# DE-140824_01.net
KiCad netlist of a schematic drawn in Altium Designer
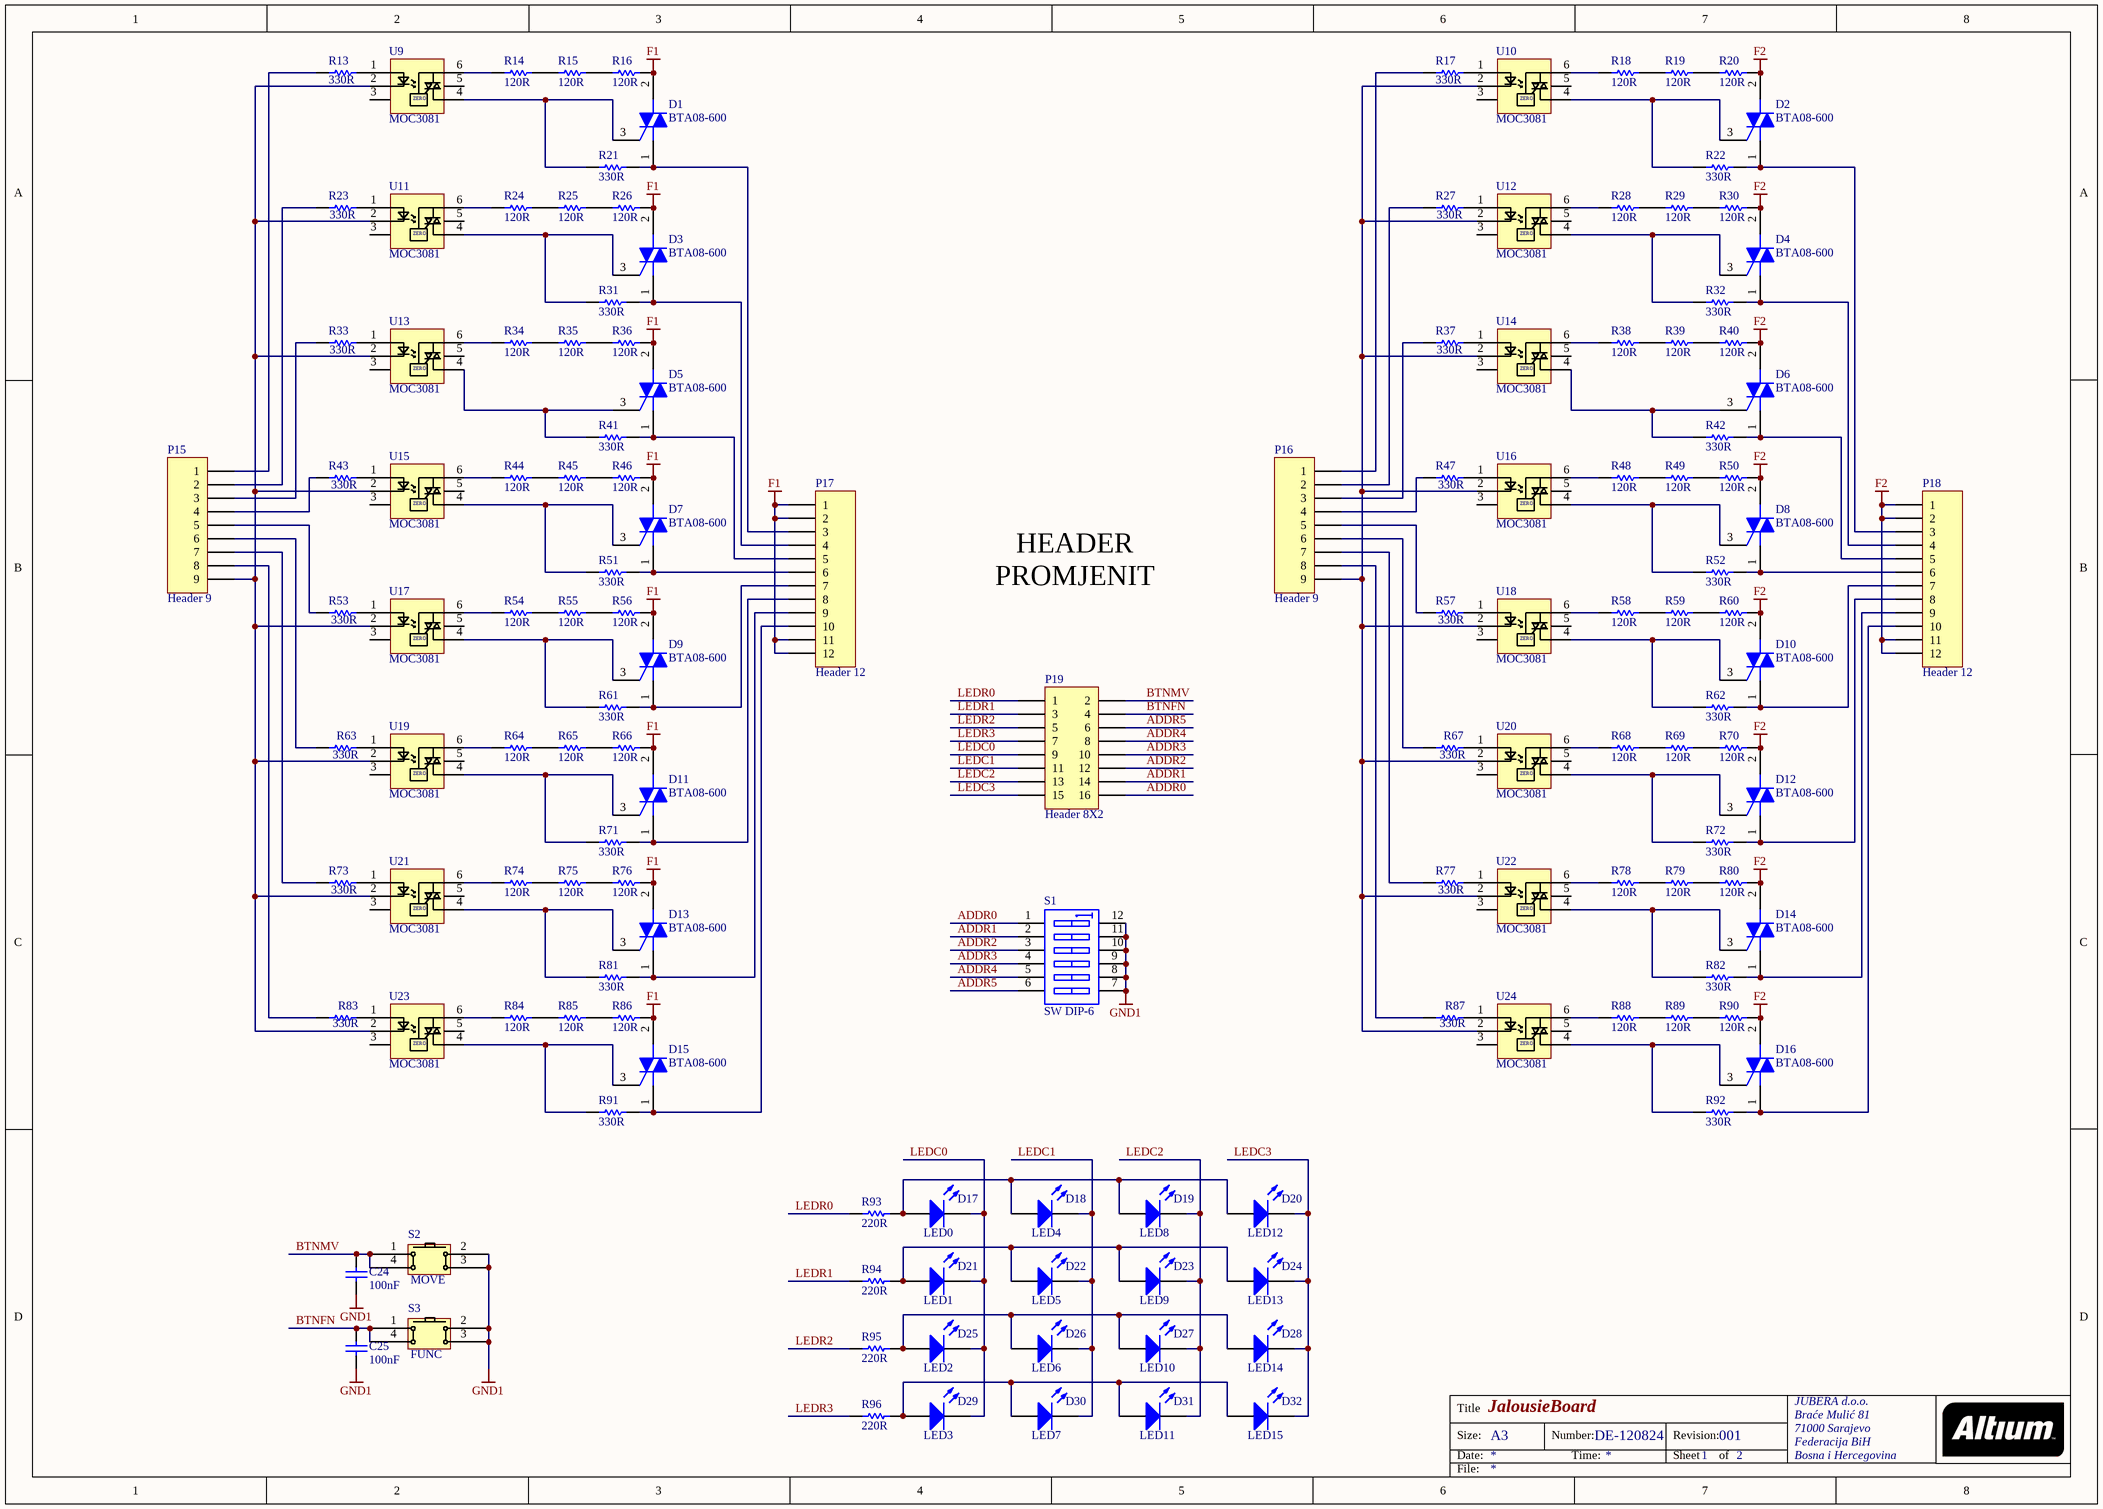
[diagram p0: DE-140824_01.SchDoc]

(export (version "E")
  (design (tool "Eeschema 10.0.6"))
  (components
    (comp (ref "C24")
      (value "100nF")
      (footprint "0603")
      (description "Ceramic Chip Capacitor - Standard")
      (fields (field (name "Comment") "C0603") (field (name "PUBLISHER") "Altium Limited"))
      (libsource (lib "DE-120824") (part "C0603"))
    )
    (comp (ref "C25")
      (value "100nF")
      (footprint "0603")
      (description "Ceramic Chip Capacitor - Standard")
      (fields (field (name "Comment") "C0603") (field (name "PUBLISHER") "Altium Limited"))
      (libsource (lib "DE-120824") (part "C0603"))
    )
    (comp (ref "D1")
      (value "BTA08-600")
      (footprint "ONSC-TO-220-3-221A-07")
      (description "Triacs, Silicon Bidirectional Thyristor, 3-Pin TO-220, Pb-Free, Tube")
      (fields (field (name "MANUFACTURER") "On Semiconductor") (field (name "PARTNUMBER") "BTA08-600BW3G"))
      (libsource (lib "DE-120824") (part "BTA08-600BW3G"))
    )
    (comp (ref "D2")
      (value "BTA08-600")
      (footprint "ONSC-TO-220-3-221A-07")
      (description "Triacs, Silicon Bidirectional Thyristor, 3-Pin TO-220, Pb-Free, Tube")
      (fields (field (name "MANUFACTURER") "On Semiconductor") (field (name "PARTNUMBER") "BTA08-600BW3G"))
      (libsource (lib "DE-120824") (part "BTA08-600BW3G"))
    )
    (comp (ref "D3")
      (value "BTA08-600")
      (footprint "ONSC-TO-220-3-221A-07")
      (description "Triacs, Silicon Bidirectional Thyristor, 3-Pin TO-220, Pb-Free, Tube")
      (fields (field (name "MANUFACTURER") "On Semiconductor") (field (name "PARTNUMBER") "BTA08-600BW3G"))
      (libsource (lib "DE-120824") (part "BTA08-600BW3G"))
    )
    (comp (ref "D4")
      (value "BTA08-600")
      (footprint "ONSC-TO-220-3-221A-07")
      (description "Triacs, Silicon Bidirectional Thyristor, 3-Pin TO-220, Pb-Free, Tube")
      (fields (field (name "MANUFACTURER") "On Semiconductor") (field (name "PARTNUMBER") "BTA08-600BW3G"))
      (libsource (lib "DE-120824") (part "BTA08-600BW3G"))
    )
    (comp (ref "D5")
      (value "BTA08-600")
      (footprint "ONSC-TO-220-3-221A-07")
      (description "Triacs, Silicon Bidirectional Thyristor, 3-Pin TO-220, Pb-Free, Tube")
      (fields (field (name "MANUFACTURER") "On Semiconductor") (field (name "PARTNUMBER") "BTA08-600BW3G"))
      (libsource (lib "DE-120824") (part "BTA08-600BW3G"))
    )
    (comp (ref "D6")
      (value "BTA08-600")
      (footprint "ONSC-TO-220-3-221A-07")
      (description "Triacs, Silicon Bidirectional Thyristor, 3-Pin TO-220, Pb-Free, Tube")
      (fields (field (name "MANUFACTURER") "On Semiconductor") (field (name "PARTNUMBER") "BTA08-600BW3G"))
      (libsource (lib "DE-120824") (part "BTA08-600BW3G"))
    )
    (comp (ref "D7")
      (value "BTA08-600")
      (footprint "ONSC-TO-220-3-221A-07")
      (description "Triacs, Silicon Bidirectional Thyristor, 3-Pin TO-220, Pb-Free, Tube")
      (fields (field (name "MANUFACTURER") "On Semiconductor") (field (name "PARTNUMBER") "BTA08-600BW3G"))
      (libsource (lib "DE-120824") (part "BTA08-600BW3G"))
    )
    (comp (ref "D8")
      (value "BTA08-600")
      (footprint "ONSC-TO-220-3-221A-07")
      (description "Triacs, Silicon Bidirectional Thyristor, 3-Pin TO-220, Pb-Free, Tube")
      (fields (field (name "MANUFACTURER") "On Semiconductor") (field (name "PARTNUMBER") "BTA08-600BW3G"))
      (libsource (lib "DE-120824") (part "BTA08-600BW3G"))
    )
    (comp (ref "D9")
      (value "BTA08-600")
      (footprint "ONSC-TO-220-3-221A-07")
      (description "Triacs, Silicon Bidirectional Thyristor, 3-Pin TO-220, Pb-Free, Tube")
      (fields (field (name "MANUFACTURER") "On Semiconductor") (field (name "PARTNUMBER") "BTA08-600BW3G"))
      (libsource (lib "DE-120824") (part "BTA08-600BW3G"))
    )
    (comp (ref "D10")
      (value "BTA08-600")
      (footprint "ONSC-TO-220-3-221A-07")
      (description "Triacs, Silicon Bidirectional Thyristor, 3-Pin TO-220, Pb-Free, Tube")
      (fields (field (name "MANUFACTURER") "On Semiconductor") (field (name "PARTNUMBER") "BTA08-600BW3G"))
      (libsource (lib "DE-120824") (part "BTA08-600BW3G"))
    )
    (comp (ref "D11")
      (value "BTA08-600")
      (footprint "ONSC-TO-220-3-221A-07")
      (description "Triacs, Silicon Bidirectional Thyristor, 3-Pin TO-220, Pb-Free, Tube")
      (fields (field (name "MANUFACTURER") "On Semiconductor") (field (name "PARTNUMBER") "BTA08-600BW3G"))
      (libsource (lib "DE-120824") (part "BTA08-600BW3G"))
    )
    (comp (ref "D12")
      (value "BTA08-600")
      (footprint "ONSC-TO-220-3-221A-07")
      (description "Triacs, Silicon Bidirectional Thyristor, 3-Pin TO-220, Pb-Free, Tube")
      (fields (field (name "MANUFACTURER") "On Semiconductor") (field (name "PARTNUMBER") "BTA08-600BW3G"))
      (libsource (lib "DE-120824") (part "BTA08-600BW3G"))
    )
    (comp (ref "D13")
      (value "BTA08-600")
      (footprint "ONSC-TO-220-3-221A-07")
      (description "Triacs, Silicon Bidirectional Thyristor, 3-Pin TO-220, Pb-Free, Tube")
      (fields (field (name "MANUFACTURER") "On Semiconductor") (field (name "PARTNUMBER") "BTA08-600BW3G"))
      (libsource (lib "DE-120824") (part "BTA08-600BW3G"))
    )
    (comp (ref "D14")
      (value "BTA08-600")
      (footprint "ONSC-TO-220-3-221A-07")
      (description "Triacs, Silicon Bidirectional Thyristor, 3-Pin TO-220, Pb-Free, Tube")
      (fields (field (name "MANUFACTURER") "On Semiconductor") (field (name "PARTNUMBER") "BTA08-600BW3G"))
      (libsource (lib "DE-120824") (part "BTA08-600BW3G"))
    )
    (comp (ref "D15")
      (value "BTA08-600")
      (footprint "ONSC-TO-220-3-221A-07")
      (description "Triacs, Silicon Bidirectional Thyristor, 3-Pin TO-220, Pb-Free, Tube")
      (fields (field (name "MANUFACTURER") "On Semiconductor") (field (name "PARTNUMBER") "BTA08-600BW3G"))
      (libsource (lib "DE-120824") (part "BTA08-600BW3G"))
    )
    (comp (ref "D16")
      (value "BTA08-600")
      (footprint "ONSC-TO-220-3-221A-07")
      (description "Triacs, Silicon Bidirectional Thyristor, 3-Pin TO-220, Pb-Free, Tube")
      (fields (field (name "MANUFACTURER") "On Semiconductor") (field (name "PARTNUMBER") "BTA08-600BW3G"))
      (libsource (lib "DE-120824") (part "BTA08-600BW3G"))
    )
    (comp (ref "D17")
      (value "LED0")
      (footprint "1.6X0.8X0.8")
      (description "Blue Surface Mount Chip LED, Blue")
      (fields (field (name "PUBLISHER") "Altium Limited"))
      (libsource (lib "DE-120824") (part "HSMB-C190"))
    )
    (comp (ref "D18")
      (value "LED4")
      (footprint "1.6X0.8X0.8")
      (description "Blue Surface Mount Chip LED, Blue")
      (fields (field (name "PUBLISHER") "Altium Limited"))
      (libsource (lib "DE-120824") (part "HSMB-C190"))
    )
    (comp (ref "D19")
      (value "LED8")
      (footprint "1.6X0.8X0.8")
      (description "Blue Surface Mount Chip LED, Blue")
      (fields (field (name "PUBLISHER") "Altium Limited"))
      (libsource (lib "DE-120824") (part "HSMB-C190"))
    )
    (comp (ref "D20")
      (value "LED12")
      (footprint "1.6X0.8X0.8")
      (description "Blue Surface Mount Chip LED, Blue")
      (fields (field (name "PUBLISHER") "Altium Limited"))
      (libsource (lib "DE-120824") (part "HSMB-C190"))
    )
    (comp (ref "D21")
      (value "LED1")
      (footprint "1.6X0.8X0.8")
      (description "Blue Surface Mount Chip LED, Blue")
      (fields (field (name "PUBLISHER") "Altium Limited"))
      (libsource (lib "DE-120824") (part "HSMB-C190"))
    )
    (comp (ref "D22")
      (value "LED5")
      (footprint "1.6X0.8X0.8")
      (description "Blue Surface Mount Chip LED, Blue")
      (fields (field (name "PUBLISHER") "Altium Limited"))
      (libsource (lib "DE-120824") (part "HSMB-C190"))
    )
    (comp (ref "D23")
      (value "LED9")
      (footprint "1.6X0.8X0.8")
      (description "Blue Surface Mount Chip LED, Blue")
      (fields (field (name "PUBLISHER") "Altium Limited"))
      (libsource (lib "DE-120824") (part "HSMB-C190"))
    )
    (comp (ref "D24")
      (value "LED13")
      (footprint "1.6X0.8X0.8")
      (description "Blue Surface Mount Chip LED, Blue")
      (fields (field (name "PUBLISHER") "Altium Limited"))
      (libsource (lib "DE-120824") (part "HSMB-C190"))
    )
    (comp (ref "D25")
      (value "LED2")
      (footprint "1.6X0.8X0.8")
      (description "Blue Surface Mount Chip LED, Blue")
      (fields (field (name "PUBLISHER") "Altium Limited"))
      (libsource (lib "DE-120824") (part "HSMB-C190"))
    )
    (comp (ref "D26")
      (value "LED6")
      (footprint "1.6X0.8X0.8")
      (description "Blue Surface Mount Chip LED, Blue")
      (fields (field (name "PUBLISHER") "Altium Limited"))
      (libsource (lib "DE-120824") (part "HSMB-C190"))
    )
    (comp (ref "D27")
      (value "LED10")
      (footprint "1.6X0.8X0.8")
      (description "Blue Surface Mount Chip LED, Blue")
      (fields (field (name "PUBLISHER") "Altium Limited"))
      (libsource (lib "DE-120824") (part "HSMB-C190"))
    )
    (comp (ref "D28")
      (value "LED14")
      (footprint "1.6X0.8X0.8")
      (description "Blue Surface Mount Chip LED, Blue")
      (fields (field (name "PUBLISHER") "Altium Limited"))
      (libsource (lib "DE-120824") (part "HSMB-C190"))
    )
    (comp (ref "D29")
      (value "LED3")
      (footprint "1.6X0.8X0.8")
      (description "Blue Surface Mount Chip LED, Blue")
      (fields (field (name "PUBLISHER") "Altium Limited"))
      (libsource (lib "DE-120824") (part "HSMB-C190"))
    )
    (comp (ref "D30")
      (value "LED7")
      (footprint "1.6X0.8X0.8")
      (description "Blue Surface Mount Chip LED, Blue")
      (fields (field (name "PUBLISHER") "Altium Limited"))
      (libsource (lib "DE-120824") (part "HSMB-C190"))
    )
    (comp (ref "D31")
      (value "LED11")
      (footprint "1.6X0.8X0.8")
      (description "Blue Surface Mount Chip LED, Blue")
      (fields (field (name "PUBLISHER") "Altium Limited"))
      (libsource (lib "DE-120824") (part "HSMB-C190"))
    )
    (comp (ref "D32")
      (value "LED15")
      (footprint "1.6X0.8X0.8")
      (description "Blue Surface Mount Chip LED, Blue")
      (fields (field (name "PUBLISHER") "Altium Limited"))
      (libsource (lib "DE-120824") (part "HSMB-C190"))
    )
    (comp (ref "P15")
      (value "Header 9")
      (footprint "HDR1X9")
      (description "Header, 9-Pin")
      (fields (field (name "PUBLISHER") "Altium Limited"))
      (libsource (lib "Miscellaneous Connectors") (part "Header 9"))
    )
    (comp (ref "P16")
      (value "Header 9")
      (footprint "HDR1X9")
      (description "Header, 9-Pin")
      (fields (field (name "PUBLISHER") "Altium Limited"))
      (libsource (lib "Miscellaneous Connectors") (part "Header 9"))
    )
    (comp (ref "P17")
      (value "Header 12")
      (footprint "HDR1X12")
      (description "Header, 12-Pin")
      (fields (field (name "PUBLISHER") "Altium Limited"))
      (libsource (lib "Miscellaneous Connectors") (part "Header 12"))
    )
    (comp (ref "P18")
      (value "Header 12")
      (footprint "HDR1X12")
      (description "Header, 12-Pin")
      (fields (field (name "PUBLISHER") "Altium Limited"))
      (libsource (lib "Miscellaneous Connectors") (part "Header 12"))
    )
    (comp (ref "P19")
      (value "Header 8X2")
      (footprint "HDR2X8")
      (description "Header, 8-Pin, Dual row")
      (fields (field (name "PUBLISHER") "Altium Limited"))
      (libsource (lib "Miscellaneous Connectors") (part "Header 8X2"))
    )
    (comp (ref "R13")
      (value "330R")
      (footprint "ERA-0603")
      (fields (field (name "PUBLISHER") "Altium Limited"))
      (libsource (lib "DE-120824") (part "ERA3Y"))
    )
    (comp (ref "R14")
      (value "120R")
      (footprint "ERA-0805")
      (fields (field (name "PUBLISHER") "Altium Limited"))
      (libsource (lib "DE-120824") (part "ERAS"))
    )
    (comp (ref "R15")
      (value "120R")
      (footprint "ERA-0805")
      (fields (field (name "PUBLISHER") "Altium Limited"))
      (libsource (lib "DE-120824") (part "ERAS"))
    )
    (comp (ref "R16")
      (value "120R")
      (footprint "ERA-0805")
      (fields (field (name "PUBLISHER") "Altium Limited"))
      (libsource (lib "DE-120824") (part "ERAS"))
    )
    (comp (ref "R17")
      (value "330R")
      (footprint "ERA-0603")
      (fields (field (name "PUBLISHER") "Altium Limited"))
      (libsource (lib "DE-120824") (part "ERA3Y"))
    )
    (comp (ref "R18")
      (value "120R")
      (footprint "ERA-0805")
      (fields (field (name "PUBLISHER") "Altium Limited"))
      (libsource (lib "DE-120824") (part "ERAS"))
    )
    (comp (ref "R19")
      (value "120R")
      (footprint "ERA-0805")
      (fields (field (name "PUBLISHER") "Altium Limited"))
      (libsource (lib "DE-120824") (part "ERAS"))
    )
    (comp (ref "R20")
      (value "120R")
      (footprint "ERA-0805")
      (fields (field (name "PUBLISHER") "Altium Limited"))
      (libsource (lib "DE-120824") (part "ERAS"))
    )
    (comp (ref "R21")
      (value "330R")
      (footprint "ERA-0805")
      (fields (field (name "PUBLISHER") "Altium Limited"))
      (libsource (lib "DE-120824") (part "ERAS"))
    )
    (comp (ref "R22")
      (value "330R")
      (footprint "ERA-0805")
      (fields (field (name "PUBLISHER") "Altium Limited"))
      (libsource (lib "DE-120824") (part "ERAS"))
    )
    (comp (ref "R23")
      (value "330R")
      (footprint "ERA-0603")
      (fields (field (name "PUBLISHER") "Altium Limited"))
      (libsource (lib "DE-120824") (part "ERA3Y"))
    )
    (comp (ref "R24")
      (value "120R")
      (footprint "ERA-0805")
      (fields (field (name "PUBLISHER") "Altium Limited"))
      (libsource (lib "DE-120824") (part "ERAS"))
    )
    (comp (ref "R25")
      (value "120R")
      (footprint "ERA-0805")
      (fields (field (name "PUBLISHER") "Altium Limited"))
      (libsource (lib "DE-120824") (part "ERAS"))
    )
    (comp (ref "R26")
      (value "120R")
      (footprint "ERA-0805")
      (fields (field (name "PUBLISHER") "Altium Limited"))
      (libsource (lib "DE-120824") (part "ERAS"))
    )
    (comp (ref "R27")
      (value "330R")
      (footprint "ERA-0603")
      (fields (field (name "PUBLISHER") "Altium Limited"))
      (libsource (lib "DE-120824") (part "ERA3Y"))
    )
    (comp (ref "R28")
      (value "120R")
      (footprint "ERA-0805")
      (fields (field (name "PUBLISHER") "Altium Limited"))
      (libsource (lib "DE-120824") (part "ERAS"))
    )
    (comp (ref "R29")
      (value "120R")
      (footprint "ERA-0805")
      (fields (field (name "PUBLISHER") "Altium Limited"))
      (libsource (lib "DE-120824") (part "ERAS"))
    )
    (comp (ref "R30")
      (value "120R")
      (footprint "ERA-0805")
      (fields (field (name "PUBLISHER") "Altium Limited"))
      (libsource (lib "DE-120824") (part "ERAS"))
    )
    (comp (ref "R31")
      (value "330R")
      (footprint "ERA-0805")
      (fields (field (name "PUBLISHER") "Altium Limited"))
      (libsource (lib "DE-120824") (part "ERAS"))
    )
    (comp (ref "R32")
      (value "330R")
      (footprint "ERA-0805")
      (fields (field (name "PUBLISHER") "Altium Limited"))
      (libsource (lib "DE-120824") (part "ERAS"))
    )
    (comp (ref "R33")
      (value "330R")
      (footprint "ERA-0603")
      (fields (field (name "PUBLISHER") "Altium Limited"))
      (libsource (lib "DE-120824") (part "ERA3Y"))
    )
    (comp (ref "R34")
      (value "120R")
      (footprint "ERA-0805")
      (fields (field (name "PUBLISHER") "Altium Limited"))
      (libsource (lib "DE-120824") (part "ERAS"))
    )
    (comp (ref "R35")
      (value "120R")
      (footprint "ERA-0805")
      (fields (field (name "PUBLISHER") "Altium Limited"))
      (libsource (lib "DE-120824") (part "ERAS"))
    )
    (comp (ref "R36")
      (value "120R")
      (footprint "ERA-0805")
      (fields (field (name "PUBLISHER") "Altium Limited"))
      (libsource (lib "DE-120824") (part "ERAS"))
    )
    (comp (ref "R37")
      (value "330R")
      (footprint "ERA-0603")
      (fields (field (name "PUBLISHER") "Altium Limited"))
      (libsource (lib "DE-120824") (part "ERA3Y"))
    )
    (comp (ref "R38")
      (value "120R")
      (footprint "ERA-0805")
      (fields (field (name "PUBLISHER") "Altium Limited"))
      (libsource (lib "DE-120824") (part "ERAS"))
    )
    (comp (ref "R39")
      (value "120R")
      (footprint "ERA-0805")
      (fields (field (name "PUBLISHER") "Altium Limited"))
      (libsource (lib "DE-120824") (part "ERAS"))
    )
    (comp (ref "R40")
      (value "120R")
      (footprint "ERA-0805")
      (fields (field (name "PUBLISHER") "Altium Limited"))
      (libsource (lib "DE-120824") (part "ERAS"))
    )
    (comp (ref "R41")
      (value "330R")
      (footprint "ERA-0805")
      (fields (field (name "PUBLISHER") "Altium Limited"))
      (libsource (lib "DE-120824") (part "ERAS"))
    )
    (comp (ref "R42")
      (value "330R")
      (footprint "ERA-0805")
      (fields (field (name "PUBLISHER") "Altium Limited"))
      (libsource (lib "DE-120824") (part "ERAS"))
    )
    (comp (ref "R43")
      (value "330R")
      (footprint "ERA-0603")
      (fields (field (name "PUBLISHER") "Altium Limited"))
      (libsource (lib "DE-120824") (part "ERA3Y"))
    )
    (comp (ref "R44")
      (value "120R")
      (footprint "ERA-0805")
      (fields (field (name "PUBLISHER") "Altium Limited"))
      (libsource (lib "DE-120824") (part "ERAS"))
    )
    (comp (ref "R45")
      (value "120R")
      (footprint "ERA-0805")
      (fields (field (name "PUBLISHER") "Altium Limited"))
      (libsource (lib "DE-120824") (part "ERAS"))
    )
    (comp (ref "R46")
      (value "120R")
      (footprint "ERA-0805")
      (fields (field (name "PUBLISHER") "Altium Limited"))
      (libsource (lib "DE-120824") (part "ERAS"))
    )
    (comp (ref "R47")
      (value "330R")
      (footprint "ERA-0603")
      (fields (field (name "PUBLISHER") "Altium Limited"))
      (libsource (lib "DE-120824") (part "ERA3Y"))
    )
    (comp (ref "R48")
      (value "120R")
      (footprint "ERA-0805")
      (fields (field (name "PUBLISHER") "Altium Limited"))
      (libsource (lib "DE-120824") (part "ERAS"))
    )
    (comp (ref "R49")
      (value "120R")
      (footprint "ERA-0805")
      (fields (field (name "PUBLISHER") "Altium Limited"))
      (libsource (lib "DE-120824") (part "ERAS"))
    )
    (comp (ref "R50")
      (value "120R")
      (footprint "ERA-0805")
      (fields (field (name "PUBLISHER") "Altium Limited"))
      (libsource (lib "DE-120824") (part "ERAS"))
    )
    (comp (ref "R51")
      (value "330R")
      (footprint "ERA-0805")
      (fields (field (name "PUBLISHER") "Altium Limited"))
      (libsource (lib "DE-120824") (part "ERAS"))
    )
    (comp (ref "R52")
      (value "330R")
      (footprint "ERA-0805")
      (fields (field (name "PUBLISHER") "Altium Limited"))
      (libsource (lib "DE-120824") (part "ERAS"))
    )
    (comp (ref "R53")
      (value "330R")
      (footprint "ERA-0603")
      (fields (field (name "PUBLISHER") "Altium Limited"))
      (libsource (lib "DE-120824") (part "ERA3Y"))
    )
    (comp (ref "R54")
      (value "120R")
      (footprint "ERA-0805")
      (fields (field (name "PUBLISHER") "Altium Limited"))
      (libsource (lib "DE-120824") (part "ERAS"))
    )
    (comp (ref "R55")
      (value "120R")
      (footprint "ERA-0805")
      (fields (field (name "PUBLISHER") "Altium Limited"))
      (libsource (lib "DE-120824") (part "ERAS"))
    )
    (comp (ref "R56")
      (value "120R")
      (footprint "ERA-0805")
      (fields (field (name "PUBLISHER") "Altium Limited"))
      (libsource (lib "DE-120824") (part "ERAS"))
    )
    (comp (ref "R57")
      (value "330R")
      (footprint "ERA-0603")
      (fields (field (name "PUBLISHER") "Altium Limited"))
      (libsource (lib "DE-120824") (part "ERA3Y"))
    )
    (comp (ref "R58")
      (value "120R")
      (footprint "ERA-0805")
      (fields (field (name "PUBLISHER") "Altium Limited"))
      (libsource (lib "DE-120824") (part "ERAS"))
    )
    (comp (ref "R59")
      (value "120R")
      (footprint "ERA-0805")
      (fields (field (name "PUBLISHER") "Altium Limited"))
      (libsource (lib "DE-120824") (part "ERAS"))
    )
    (comp (ref "R60")
      (value "120R")
      (footprint "ERA-0805")
      (fields (field (name "PUBLISHER") "Altium Limited"))
      (libsource (lib "DE-120824") (part "ERAS"))
    )
    (comp (ref "R61")
      (value "330R")
      (footprint "ERA-0805")
      (fields (field (name "PUBLISHER") "Altium Limited"))
      (libsource (lib "DE-120824") (part "ERAS"))
    )
    (comp (ref "R62")
      (value "330R")
      (footprint "ERA-0805")
      (fields (field (name "PUBLISHER") "Altium Limited"))
      (libsource (lib "DE-120824") (part "ERAS"))
    )
    (comp (ref "R63")
      (value "330R")
      (footprint "ERA-0603")
      (fields (field (name "PUBLISHER") "Altium Limited"))
      (libsource (lib "DE-120824") (part "ERA3Y"))
    )
    (comp (ref "R64")
      (value "120R")
      (footprint "ERA-0805")
      (fields (field (name "PUBLISHER") "Altium Limited"))
      (libsource (lib "DE-120824") (part "ERAS"))
    )
    (comp (ref "R65")
      (value "120R")
      (footprint "ERA-0805")
      (fields (field (name "PUBLISHER") "Altium Limited"))
      (libsource (lib "DE-120824") (part "ERAS"))
    )
    (comp (ref "R66")
      (value "120R")
      (footprint "ERA-0805")
      (fields (field (name "PUBLISHER") "Altium Limited"))
      (libsource (lib "DE-120824") (part "ERAS"))
    )
    (comp (ref "R67")
      (value "330R")
      (footprint "ERA-0603")
      (fields (field (name "PUBLISHER") "Altium Limited"))
      (libsource (lib "DE-120824") (part "ERA3Y"))
    )
    (comp (ref "R68")
      (value "120R")
      (footprint "ERA-0805")
      (fields (field (name "PUBLISHER") "Altium Limited"))
      (libsource (lib "DE-120824") (part "ERAS"))
    )
    (comp (ref "R69")
      (value "120R")
      (footprint "ERA-0805")
      (fields (field (name "PUBLISHER") "Altium Limited"))
      (libsource (lib "DE-120824") (part "ERAS"))
    )
    (comp (ref "R70")
      (value "120R")
      (footprint "ERA-0805")
      (fields (field (name "PUBLISHER") "Altium Limited"))
      (libsource (lib "DE-120824") (part "ERAS"))
    )
    (comp (ref "R71")
      (value "330R")
      (footprint "ERA-0805")
      (fields (field (name "PUBLISHER") "Altium Limited"))
      (libsource (lib "DE-120824") (part "ERAS"))
    )
    (comp (ref "R72")
      (value "330R")
      (footprint "ERA-0805")
      (fields (field (name "PUBLISHER") "Altium Limited"))
      (libsource (lib "DE-120824") (part "ERAS"))
    )
    (comp (ref "R73")
      (value "330R")
      (footprint "ERA-0603")
      (fields (field (name "PUBLISHER") "Altium Limited"))
      (libsource (lib "DE-120824") (part "ERA3Y"))
    )
    (comp (ref "R74")
      (value "120R")
      (footprint "ERA-0805")
      (fields (field (name "PUBLISHER") "Altium Limited"))
      (libsource (lib "DE-120824") (part "ERAS"))
    )
    (comp (ref "R75")
      (value "120R")
      (footprint "ERA-0805")
      (fields (field (name "PUBLISHER") "Altium Limited"))
      (libsource (lib "DE-120824") (part "ERAS"))
    )
    (comp (ref "R76")
      (value "120R")
      (footprint "ERA-0805")
      (fields (field (name "PUBLISHER") "Altium Limited"))
      (libsource (lib "DE-120824") (part "ERAS"))
    )
    (comp (ref "R77")
      (value "330R")
      (footprint "ERA-0603")
      (fields (field (name "PUBLISHER") "Altium Limited"))
      (libsource (lib "DE-120824") (part "ERA3Y"))
    )
    (comp (ref "R78")
      (value "120R")
      (footprint "ERA-0805")
      (fields (field (name "PUBLISHER") "Altium Limited"))
      (libsource (lib "DE-120824") (part "ERAS"))
    )
    (comp (ref "R79")
      (value "120R")
      (footprint "ERA-0805")
      (fields (field (name "PUBLISHER") "Altium Limited"))
      (libsource (lib "DE-120824") (part "ERAS"))
    )
    (comp (ref "R80")
      (value "120R")
      (footprint "ERA-0805")
      (fields (field (name "PUBLISHER") "Altium Limited"))
      (libsource (lib "DE-120824") (part "ERAS"))
    )
    (comp (ref "R81")
      (value "330R")
      (footprint "ERA-0805")
      (fields (field (name "PUBLISHER") "Altium Limited"))
      (libsource (lib "DE-120824") (part "ERAS"))
    )
    (comp (ref "R82")
      (value "330R")
      (footprint "ERA-0805")
      (fields (field (name "PUBLISHER") "Altium Limited"))
      (libsource (lib "DE-120824") (part "ERAS"))
    )
    (comp (ref "R83")
      (value "330R")
      (footprint "ERA-0603")
      (fields (field (name "PUBLISHER") "Altium Limited"))
      (libsource (lib "DE-120824") (part "ERA3Y"))
    )
    (comp (ref "R84")
      (value "120R")
      (footprint "ERA-0805")
      (fields (field (name "PUBLISHER") "Altium Limited"))
      (libsource (lib "DE-120824") (part "ERAS"))
    )
    (comp (ref "R85")
      (value "120R")
      (footprint "ERA-0805")
      (fields (field (name "PUBLISHER") "Altium Limited"))
      (libsource (lib "DE-120824") (part "ERAS"))
    )
    (comp (ref "R86")
      (value "120R")
      (footprint "ERA-0805")
      (fields (field (name "PUBLISHER") "Altium Limited"))
      (libsource (lib "DE-120824") (part "ERAS"))
    )
    (comp (ref "R87")
      (value "330R")
      (footprint "ERA-0603")
      (fields (field (name "PUBLISHER") "Altium Limited"))
      (libsource (lib "DE-120824") (part "ERA3Y"))
    )
    (comp (ref "R88")
      (value "120R")
      (footprint "ERA-0805")
      (fields (field (name "PUBLISHER") "Altium Limited"))
      (libsource (lib "DE-120824") (part "ERAS"))
    )
    (comp (ref "R89")
      (value "120R")
      (footprint "ERA-0805")
      (fields (field (name "PUBLISHER") "Altium Limited"))
      (libsource (lib "DE-120824") (part "ERAS"))
    )
    (comp (ref "R90")
      (value "120R")
      (footprint "ERA-0805")
      (fields (field (name "PUBLISHER") "Altium Limited"))
      (libsource (lib "DE-120824") (part "ERAS"))
    )
    (comp (ref "R91")
      (value "330R")
      (footprint "ERA-0805")
      (fields (field (name "PUBLISHER") "Altium Limited"))
      (libsource (lib "DE-120824") (part "ERAS"))
    )
    (comp (ref "R92")
      (value "330R")
      (footprint "ERA-0805")
      (fields (field (name "PUBLISHER") "Altium Limited"))
      (libsource (lib "DE-120824") (part "ERAS"))
    )
    (comp (ref "R93")
      (value "220R")
      (footprint "ERA-0603")
      (fields (field (name "PUBLISHER") "Altium Limited"))
      (libsource (lib "DE-120824") (part "ERAS"))
    )
    (comp (ref "R94")
      (value "220R")
      (footprint "ERA-0603")
      (fields (field (name "PUBLISHER") "Altium Limited"))
      (libsource (lib "DE-120824") (part "ERAS"))
    )
    (comp (ref "R95")
      (value "220R")
      (footprint "ERA-0603")
      (fields (field (name "PUBLISHER") "Altium Limited"))
      (libsource (lib "DE-120824") (part "ERAS"))
    )
    (comp (ref "R96")
      (value "220R")
      (footprint "ERA-0603")
      (fields (field (name "PUBLISHER") "Altium Limited"))
      (libsource (lib "DE-120824") (part "ERAS"))
    )
    (comp (ref "S1")
      (value "SW DIP-6")
      (footprint "DIP-12/SW")
      (description "DIP Switch, 6 Position, SPST")
      (fields (field (name "PUBLISHER") "Altium Limited"))
      (libsource (lib "Miscellaneous Devices") (part "SW DIP-6"))
    )
    (comp (ref "S2")
      (value "MOVE")
      (footprint "TACTILE_SWITCH")
      (libsource (lib "DE-120824") (part "TACKTILE_SWITCH"))
    )
    (comp (ref "S3")
      (value "FUNC")
      (footprint "TACTILE_SWITCH")
      (libsource (lib "DE-120824") (part "TACKTILE_SWITCH"))
    )
    (comp (ref "U9")
      (value "MOC3081")
      (footprint "DIP6")
      (description "Zero-Cross Optoisolator Triac Driver")
      (libsource (lib "DE-120824") (part "MOC3081"))
    )
    (comp (ref "U10")
      (value "MOC3081")
      (footprint "DIP6")
      (description "Zero-Cross Optoisolator Triac Driver")
      (libsource (lib "DE-120824") (part "MOC3081"))
    )
    (comp (ref "U11")
      (value "MOC3081")
      (footprint "DIP6")
      (description "Zero-Cross Optoisolator Triac Driver")
      (libsource (lib "DE-120824") (part "MOC3081"))
    )
    (comp (ref "U12")
      (value "MOC3081")
      (footprint "DIP6")
      (description "Zero-Cross Optoisolator Triac Driver")
      (libsource (lib "DE-120824") (part "MOC3081"))
    )
    (comp (ref "U13")
      (value "MOC3081")
      (footprint "DIP6")
      (description "Zero-Cross Optoisolator Triac Driver")
      (libsource (lib "DE-120824") (part "MOC3081"))
    )
    (comp (ref "U14")
      (value "MOC3081")
      (footprint "DIP6")
      (description "Zero-Cross Optoisolator Triac Driver")
      (libsource (lib "DE-120824") (part "MOC3081"))
    )
    (comp (ref "U15")
      (value "MOC3081")
      (footprint "DIP6")
      (description "Zero-Cross Optoisolator Triac Driver")
      (libsource (lib "DE-120824") (part "MOC3081"))
    )
    (comp (ref "U16")
      (value "MOC3081")
      (footprint "DIP6")
      (description "Zero-Cross Optoisolator Triac Driver")
      (libsource (lib "DE-120824") (part "MOC3081"))
    )
    (comp (ref "U17")
      (value "MOC3081")
      (footprint "DIP6")
      (description "Zero-Cross Optoisolator Triac Driver")
      (libsource (lib "DE-120824") (part "MOC3081"))
    )
    (comp (ref "U18")
      (value "MOC3081")
      (footprint "DIP6")
      (description "Zero-Cross Optoisolator Triac Driver")
      (libsource (lib "DE-120824") (part "MOC3081"))
    )
    (comp (ref "U19")
      (value "MOC3081")
      (footprint "DIP6")
      (description "Zero-Cross Optoisolator Triac Driver")
      (libsource (lib "DE-120824") (part "MOC3081"))
    )
    (comp (ref "U20")
      (value "MOC3081")
      (footprint "DIP6")
      (description "Zero-Cross Optoisolator Triac Driver")
      (libsource (lib "DE-120824") (part "MOC3081"))
    )
    (comp (ref "U21")
      (value "MOC3081")
      (footprint "DIP6")
      (description "Zero-Cross Optoisolator Triac Driver")
      (libsource (lib "DE-120824") (part "MOC3081"))
    )
    (comp (ref "U22")
      (value "MOC3081")
      (footprint "DIP6")
      (description "Zero-Cross Optoisolator Triac Driver")
      (libsource (lib "DE-120824") (part "MOC3081"))
    )
    (comp (ref "U23")
      (value "MOC3081")
      (footprint "DIP6")
      (description "Zero-Cross Optoisolator Triac Driver")
      (libsource (lib "DE-120824") (part "MOC3081"))
    )
    (comp (ref "U24")
      (value "MOC3081")
      (footprint "DIP6")
      (description "Zero-Cross Optoisolator Triac Driver")
      (libsource (lib "DE-120824") (part "MOC3081"))
    )
  )
  (nets
    (net (code "1") (name "/ADDR0") (class "Default")
      (node (ref "P19") (pin "16") (pinfunction "16_16") (pintype "passive"))
      (node (ref "S1") (pin "1") (pinfunction "A1_1") (pintype "passive"))
    )
    (net (code "2") (name "/ADDR1") (class "Default")
      (node (ref "P19") (pin "14") (pinfunction "14_14") (pintype "passive"))
      (node (ref "S1") (pin "2") (pinfunction "A2_2") (pintype "passive"))
    )
    (net (code "3") (name "/ADDR2") (class "Default")
      (node (ref "P19") (pin "12") (pinfunction "12_12") (pintype "passive"))
      (node (ref "S1") (pin "3") (pinfunction "A3_3") (pintype "passive"))
    )
    (net (code "4") (name "/ADDR3") (class "Default")
      (node (ref "P19") (pin "10") (pinfunction "10_10") (pintype "passive"))
      (node (ref "S1") (pin "4") (pinfunction "A4_4") (pintype "passive"))
    )
    (net (code "5") (name "/ADDR4") (class "Default")
      (node (ref "P19") (pin "8") (pinfunction "8_8") (pintype "passive"))
      (node (ref "S1") (pin "5") (pinfunction "A5_5") (pintype "passive"))
    )
    (net (code "6") (name "/ADDR5") (class "Default")
      (node (ref "P19") (pin "6") (pinfunction "6_6") (pintype "passive"))
      (node (ref "S1") (pin "6") (pinfunction "A6_6") (pintype "passive"))
    )
    (net (code "7") (name "/BTNFN") (class "Default")
      (node (ref "C25") (pin "1") (pinfunction "1_1") (pintype "passive"))
      (node (ref "P19") (pin "4") (pinfunction "4_4") (pintype "passive"))
      (node (ref "S3") (pin "1") (pinfunction "1_1") (pintype "passive"))
      (node (ref "S3") (pin "4") (pinfunction "4_4") (pintype "passive"))
    )
    (net (code "8") (name "/BTNMV") (class "Default")
      (node (ref "C24") (pin "1") (pinfunction "1_1") (pintype "passive"))
      (node (ref "P19") (pin "2") (pinfunction "2_2") (pintype "passive"))
      (node (ref "S2") (pin "1") (pinfunction "1_1") (pintype "passive"))
      (node (ref "S2") (pin "4") (pinfunction "4_4") (pintype "passive"))
    )
    (net (code "9") (name "/LEDC0") (class "Default")
      (node (ref "D17") (pin "2") (pinfunction "K_2") (pintype "passive"))
      (node (ref "D21") (pin "2") (pinfunction "K_2") (pintype "passive"))
      (node (ref "D25") (pin "2") (pinfunction "K_2") (pintype "passive"))
      (node (ref "D29") (pin "2") (pinfunction "K_2") (pintype "passive"))
      (node (ref "P19") (pin "9") (pinfunction "9_9") (pintype "passive"))
    )
    (net (code "10") (name "/LEDC1") (class "Default")
      (node (ref "D18") (pin "2") (pinfunction "K_2") (pintype "passive"))
      (node (ref "D22") (pin "2") (pinfunction "K_2") (pintype "passive"))
      (node (ref "D26") (pin "2") (pinfunction "K_2") (pintype "passive"))
      (node (ref "D30") (pin "2") (pinfunction "K_2") (pintype "passive"))
      (node (ref "P19") (pin "11") (pinfunction "11_11") (pintype "passive"))
    )
    (net (code "11") (name "/LEDC2") (class "Default")
      (node (ref "D19") (pin "2") (pinfunction "K_2") (pintype "passive"))
      (node (ref "D23") (pin "2") (pinfunction "K_2") (pintype "passive"))
      (node (ref "D27") (pin "2") (pinfunction "K_2") (pintype "passive"))
      (node (ref "D31") (pin "2") (pinfunction "K_2") (pintype "passive"))
      (node (ref "P19") (pin "13") (pinfunction "13_13") (pintype "passive"))
    )
    (net (code "12") (name "/LEDC3") (class "Default")
      (node (ref "D20") (pin "2") (pinfunction "K_2") (pintype "passive"))
      (node (ref "D24") (pin "2") (pinfunction "K_2") (pintype "passive"))
      (node (ref "D28") (pin "2") (pinfunction "K_2") (pintype "passive"))
      (node (ref "D32") (pin "2") (pinfunction "K_2") (pintype "passive"))
      (node (ref "P19") (pin "15") (pinfunction "15_15") (pintype "passive"))
    )
    (net (code "13") (name "/LEDR0") (class "Default")
      (node (ref "P19") (pin "1") (pinfunction "1_1") (pintype "passive"))
      (node (ref "R93") (pin "1") (pinfunction "1_1") (pintype "passive"))
    )
    (net (code "14") (name "/LEDR1") (class "Default")
      (node (ref "P19") (pin "3") (pinfunction "3_3") (pintype "passive"))
      (node (ref "R94") (pin "1") (pinfunction "1_1") (pintype "passive"))
    )
    (net (code "15") (name "/LEDR2") (class "Default")
      (node (ref "P19") (pin "5") (pinfunction "5_5") (pintype "passive"))
      (node (ref "R95") (pin "1") (pinfunction "1_1") (pintype "passive"))
    )
    (net (code "16") (name "/LEDR3") (class "Default")
      (node (ref "P19") (pin "7") (pinfunction "7_7") (pintype "passive"))
      (node (ref "R96") (pin "1") (pinfunction "1_1") (pintype "passive"))
    )
    (net (code "17") (name "F1") (class "Default")
      (node (ref "D1") (pin "2") (pinfunction "MT2_2") (pintype "passive"))
      (node (ref "D11") (pin "2") (pinfunction "MT2_2") (pintype "passive"))
      (node (ref "D13") (pin "2") (pinfunction "MT2_2") (pintype "passive"))
      (node (ref "D15") (pin "2") (pinfunction "MT2_2") (pintype "passive"))
      (node (ref "D3") (pin "2") (pinfunction "MT2_2") (pintype "passive"))
      (node (ref "D5") (pin "2") (pinfunction "MT2_2") (pintype "passive"))
      (node (ref "D7") (pin "2") (pinfunction "MT2_2") (pintype "passive"))
      (node (ref "D9") (pin "2") (pinfunction "MT2_2") (pintype "passive"))
      (node (ref "P17") (pin "1") (pinfunction "1_1") (pintype "passive"))
      (node (ref "P17") (pin "11") (pinfunction "11_11") (pintype "passive"))
      (node (ref "P17") (pin "12") (pinfunction "12_12") (pintype "passive"))
      (node (ref "P17") (pin "2") (pinfunction "2_2") (pintype "passive"))
      (node (ref "R16") (pin "2") (pinfunction "2_2") (pintype "passive"))
      (node (ref "R26") (pin "2") (pinfunction "2_2") (pintype "passive"))
      (node (ref "R36") (pin "2") (pinfunction "2_2") (pintype "passive"))
      (node (ref "R46") (pin "2") (pinfunction "2_2") (pintype "passive"))
      (node (ref "R56") (pin "2") (pinfunction "2_2") (pintype "passive"))
      (node (ref "R66") (pin "2") (pinfunction "2_2") (pintype "passive"))
      (node (ref "R76") (pin "2") (pinfunction "2_2") (pintype "passive"))
      (node (ref "R86") (pin "2") (pinfunction "2_2") (pintype "passive"))
    )
    (net (code "18") (name "F2") (class "Default")
      (node (ref "D10") (pin "2") (pinfunction "MT2_2") (pintype "passive"))
      (node (ref "D12") (pin "2") (pinfunction "MT2_2") (pintype "passive"))
      (node (ref "D14") (pin "2") (pinfunction "MT2_2") (pintype "passive"))
      (node (ref "D16") (pin "2") (pinfunction "MT2_2") (pintype "passive"))
      (node (ref "D2") (pin "2") (pinfunction "MT2_2") (pintype "passive"))
      (node (ref "D4") (pin "2") (pinfunction "MT2_2") (pintype "passive"))
      (node (ref "D6") (pin "2") (pinfunction "MT2_2") (pintype "passive"))
      (node (ref "D8") (pin "2") (pinfunction "MT2_2") (pintype "passive"))
      (node (ref "P18") (pin "1") (pinfunction "1_1") (pintype "passive"))
      (node (ref "P18") (pin "11") (pinfunction "11_11") (pintype "passive"))
      (node (ref "P18") (pin "12") (pinfunction "12_12") (pintype "passive"))
      (node (ref "P18") (pin "2") (pinfunction "2_2") (pintype "passive"))
      (node (ref "R20") (pin "2") (pinfunction "2_2") (pintype "passive"))
      (node (ref "R30") (pin "2") (pinfunction "2_2") (pintype "passive"))
      (node (ref "R40") (pin "2") (pinfunction "2_2") (pintype "passive"))
      (node (ref "R50") (pin "2") (pinfunction "2_2") (pintype "passive"))
      (node (ref "R60") (pin "2") (pinfunction "2_2") (pintype "passive"))
      (node (ref "R70") (pin "2") (pinfunction "2_2") (pintype "passive"))
      (node (ref "R80") (pin "2") (pinfunction "2_2") (pintype "passive"))
      (node (ref "R90") (pin "2") (pinfunction "2_2") (pintype "passive"))
    )
    (net (code "19") (name "GND1") (class "Default")
      (node (ref "C24") (pin "2") (pinfunction "2_2") (pintype "passive"))
      (node (ref "C25") (pin "2") (pinfunction "2_2") (pintype "passive"))
      (node (ref "S1") (pin "10") (pinfunction "B3_10") (pintype "passive"))
      (node (ref "S1") (pin "11") (pinfunction "B2_11") (pintype "passive"))
      (node (ref "S1") (pin "12") (pinfunction "B1_12") (pintype "passive"))
      (node (ref "S1") (pin "7") (pinfunction "B6_7") (pintype "passive"))
      (node (ref "S1") (pin "8") (pinfunction "B5_8") (pintype "passive"))
      (node (ref "S1") (pin "9") (pinfunction "B4_9") (pintype "passive"))
      (node (ref "S2") (pin "2") (pinfunction "2_2") (pintype "passive"))
      (node (ref "S2") (pin "3") (pinfunction "3_3") (pintype "passive"))
      (node (ref "S3") (pin "2") (pinfunction "2_2") (pintype "passive"))
      (node (ref "S3") (pin "3") (pinfunction "3_3") (pintype "passive"))
    )
    (net (code "20") (name "Net-(D1-G)") (class "Default")
      (node (ref "D1") (pin "3") (pinfunction "G_3") (pintype "passive"))
      (node (ref "R21") (pin "1") (pinfunction "1_1") (pintype "passive"))
      (node (ref "U9") (pin "4") (pinfunction "4_4") (pintype "passive"))
    )
    (net (code "21") (name "Net-(D1-MT1)") (class "Default")
      (node (ref "D1") (pin "1") (pinfunction "MT1_1") (pintype "passive"))
      (node (ref "P17") (pin "3") (pinfunction "3_3") (pintype "passive"))
      (node (ref "R21") (pin "2") (pinfunction "2_2") (pintype "passive"))
    )
    (net (code "22") (name "Net-(D2-G)") (class "Default")
      (node (ref "D2") (pin "3") (pinfunction "G_3") (pintype "passive"))
      (node (ref "R22") (pin "1") (pinfunction "1_1") (pintype "passive"))
      (node (ref "U10") (pin "4") (pinfunction "4_4") (pintype "passive"))
    )
    (net (code "23") (name "Net-(D2-MT1)") (class "Default")
      (node (ref "D2") (pin "1") (pinfunction "MT1_1") (pintype "passive"))
      (node (ref "P18") (pin "3") (pinfunction "3_3") (pintype "passive"))
      (node (ref "R22") (pin "2") (pinfunction "2_2") (pintype "passive"))
    )
    (net (code "24") (name "Net-(D3-G)") (class "Default")
      (node (ref "D3") (pin "3") (pinfunction "G_3") (pintype "passive"))
      (node (ref "R31") (pin "1") (pinfunction "1_1") (pintype "passive"))
      (node (ref "U11") (pin "4") (pinfunction "4_4") (pintype "passive"))
    )
    (net (code "25") (name "Net-(D3-MT1)") (class "Default")
      (node (ref "D3") (pin "1") (pinfunction "MT1_1") (pintype "passive"))
      (node (ref "P17") (pin "4") (pinfunction "4_4") (pintype "passive"))
      (node (ref "R31") (pin "2") (pinfunction "2_2") (pintype "passive"))
    )
    (net (code "26") (name "Net-(D4-G)") (class "Default")
      (node (ref "D4") (pin "3") (pinfunction "G_3") (pintype "passive"))
      (node (ref "R32") (pin "1") (pinfunction "1_1") (pintype "passive"))
      (node (ref "U12") (pin "4") (pinfunction "4_4") (pintype "passive"))
    )
    (net (code "27") (name "Net-(D4-MT1)") (class "Default")
      (node (ref "D4") (pin "1") (pinfunction "MT1_1") (pintype "passive"))
      (node (ref "P18") (pin "4") (pinfunction "4_4") (pintype "passive"))
      (node (ref "R32") (pin "2") (pinfunction "2_2") (pintype "passive"))
    )
    (net (code "28") (name "Net-(D5-G)") (class "Default")
      (node (ref "D5") (pin "3") (pinfunction "G_3") (pintype "passive"))
      (node (ref "R41") (pin "1") (pinfunction "1_1") (pintype "passive"))
      (node (ref "U13") (pin "4") (pinfunction "4_4") (pintype "passive"))
    )
    (net (code "29") (name "Net-(D5-MT1)") (class "Default")
      (node (ref "D5") (pin "1") (pinfunction "MT1_1") (pintype "passive"))
      (node (ref "P17") (pin "5") (pinfunction "5_5") (pintype "passive"))
      (node (ref "R41") (pin "2") (pinfunction "2_2") (pintype "passive"))
    )
    (net (code "30") (name "Net-(D6-G)") (class "Default")
      (node (ref "D6") (pin "3") (pinfunction "G_3") (pintype "passive"))
      (node (ref "R42") (pin "1") (pinfunction "1_1") (pintype "passive"))
      (node (ref "U14") (pin "4") (pinfunction "4_4") (pintype "passive"))
    )
    (net (code "31") (name "Net-(D6-MT1)") (class "Default")
      (node (ref "D6") (pin "1") (pinfunction "MT1_1") (pintype "passive"))
      (node (ref "P18") (pin "5") (pinfunction "5_5") (pintype "passive"))
      (node (ref "R42") (pin "2") (pinfunction "2_2") (pintype "passive"))
    )
    (net (code "32") (name "Net-(D7-G)") (class "Default")
      (node (ref "D7") (pin "3") (pinfunction "G_3") (pintype "passive"))
      (node (ref "R51") (pin "1") (pinfunction "1_1") (pintype "passive"))
      (node (ref "U15") (pin "4") (pinfunction "4_4") (pintype "passive"))
    )
    (net (code "33") (name "Net-(D7-MT1)") (class "Default")
      (node (ref "D7") (pin "1") (pinfunction "MT1_1") (pintype "passive"))
      (node (ref "P17") (pin "6") (pinfunction "6_6") (pintype "passive"))
      (node (ref "R51") (pin "2") (pinfunction "2_2") (pintype "passive"))
    )
    (net (code "34") (name "Net-(D8-G)") (class "Default")
      (node (ref "D8") (pin "3") (pinfunction "G_3") (pintype "passive"))
      (node (ref "R52") (pin "1") (pinfunction "1_1") (pintype "passive"))
      (node (ref "U16") (pin "4") (pinfunction "4_4") (pintype "passive"))
    )
    (net (code "35") (name "Net-(D8-MT1)") (class "Default")
      (node (ref "D8") (pin "1") (pinfunction "MT1_1") (pintype "passive"))
      (node (ref "P18") (pin "6") (pinfunction "6_6") (pintype "passive"))
      (node (ref "R52") (pin "2") (pinfunction "2_2") (pintype "passive"))
    )
    (net (code "36") (name "Net-(D9-G)") (class "Default")
      (node (ref "D9") (pin "3") (pinfunction "G_3") (pintype "passive"))
      (node (ref "R61") (pin "1") (pinfunction "1_1") (pintype "passive"))
      (node (ref "U17") (pin "4") (pinfunction "4_4") (pintype "passive"))
    )
    (net (code "37") (name "Net-(D9-MT1)") (class "Default")
      (node (ref "D9") (pin "1") (pinfunction "MT1_1") (pintype "passive"))
      (node (ref "P17") (pin "7") (pinfunction "7_7") (pintype "passive"))
      (node (ref "R61") (pin "2") (pinfunction "2_2") (pintype "passive"))
    )
    (net (code "38") (name "Net-(D10-G)") (class "Default")
      (node (ref "D10") (pin "3") (pinfunction "G_3") (pintype "passive"))
      (node (ref "R62") (pin "1") (pinfunction "1_1") (pintype "passive"))
      (node (ref "U18") (pin "4") (pinfunction "4_4") (pintype "passive"))
    )
    (net (code "39") (name "Net-(D10-MT1)") (class "Default")
      (node (ref "D10") (pin "1") (pinfunction "MT1_1") (pintype "passive"))
      (node (ref "P18") (pin "7") (pinfunction "7_7") (pintype "passive"))
      (node (ref "R62") (pin "2") (pinfunction "2_2") (pintype "passive"))
    )
    (net (code "40") (name "Net-(D11-G)") (class "Default")
      (node (ref "D11") (pin "3") (pinfunction "G_3") (pintype "passive"))
      (node (ref "R71") (pin "1") (pinfunction "1_1") (pintype "passive"))
      (node (ref "U19") (pin "4") (pinfunction "4_4") (pintype "passive"))
    )
    (net (code "41") (name "Net-(D11-MT1)") (class "Default")
      (node (ref "D11") (pin "1") (pinfunction "MT1_1") (pintype "passive"))
      (node (ref "P17") (pin "8") (pinfunction "8_8") (pintype "passive"))
      (node (ref "R71") (pin "2") (pinfunction "2_2") (pintype "passive"))
    )
    (net (code "42") (name "Net-(D12-G)") (class "Default")
      (node (ref "D12") (pin "3") (pinfunction "G_3") (pintype "passive"))
      (node (ref "R72") (pin "1") (pinfunction "1_1") (pintype "passive"))
      (node (ref "U20") (pin "4") (pinfunction "4_4") (pintype "passive"))
    )
    (net (code "43") (name "Net-(D12-MT1)") (class "Default")
      (node (ref "D12") (pin "1") (pinfunction "MT1_1") (pintype "passive"))
      (node (ref "P18") (pin "8") (pinfunction "8_8") (pintype "passive"))
      (node (ref "R72") (pin "2") (pinfunction "2_2") (pintype "passive"))
    )
    (net (code "44") (name "Net-(D13-G)") (class "Default")
      (node (ref "D13") (pin "3") (pinfunction "G_3") (pintype "passive"))
      (node (ref "R81") (pin "1") (pinfunction "1_1") (pintype "passive"))
      (node (ref "U21") (pin "4") (pinfunction "4_4") (pintype "passive"))
    )
    (net (code "45") (name "Net-(D13-MT1)") (class "Default")
      (node (ref "D13") (pin "1") (pinfunction "MT1_1") (pintype "passive"))
      (node (ref "P17") (pin "9") (pinfunction "9_9") (pintype "passive"))
      (node (ref "R81") (pin "2") (pinfunction "2_2") (pintype "passive"))
    )
    (net (code "46") (name "Net-(D14-G)") (class "Default")
      (node (ref "D14") (pin "3") (pinfunction "G_3") (pintype "passive"))
      (node (ref "R82") (pin "1") (pinfunction "1_1") (pintype "passive"))
      (node (ref "U22") (pin "4") (pinfunction "4_4") (pintype "passive"))
    )
    (net (code "47") (name "Net-(D14-MT1)") (class "Default")
      (node (ref "D14") (pin "1") (pinfunction "MT1_1") (pintype "passive"))
      (node (ref "P18") (pin "9") (pinfunction "9_9") (pintype "passive"))
      (node (ref "R82") (pin "2") (pinfunction "2_2") (pintype "passive"))
    )
    (net (code "48") (name "Net-(D15-G)") (class "Default")
      (node (ref "D15") (pin "3") (pinfunction "G_3") (pintype "passive"))
      (node (ref "R91") (pin "1") (pinfunction "1_1") (pintype "passive"))
      (node (ref "U23") (pin "4") (pinfunction "4_4") (pintype "passive"))
    )
    (net (code "49") (name "Net-(D15-MT1)") (class "Default")
      (node (ref "D15") (pin "1") (pinfunction "MT1_1") (pintype "passive"))
      (node (ref "P17") (pin "10") (pinfunction "10_10") (pintype "passive"))
      (node (ref "R91") (pin "2") (pinfunction "2_2") (pintype "passive"))
    )
    (net (code "50") (name "Net-(D16-G)") (class "Default")
      (node (ref "D16") (pin "3") (pinfunction "G_3") (pintype "passive"))
      (node (ref "R92") (pin "1") (pinfunction "1_1") (pintype "passive"))
      (node (ref "U24") (pin "4") (pinfunction "4_4") (pintype "passive"))
    )
    (net (code "51") (name "Net-(D16-MT1)") (class "Default")
      (node (ref "D16") (pin "1") (pinfunction "MT1_1") (pintype "passive"))
      (node (ref "P18") (pin "10") (pinfunction "10_10") (pintype "passive"))
      (node (ref "R92") (pin "2") (pinfunction "2_2") (pintype "passive"))
    )
    (net (code "52") (name "Net-(D17-A)") (class "Default")
      (node (ref "D17") (pin "1") (pinfunction "A_1") (pintype "passive"))
      (node (ref "D18") (pin "1") (pinfunction "A_1") (pintype "passive"))
      (node (ref "D19") (pin "1") (pinfunction "A_1") (pintype "passive"))
      (node (ref "D20") (pin "1") (pinfunction "A_1") (pintype "passive"))
      (node (ref "R93") (pin "2") (pinfunction "2_2") (pintype "passive"))
    )
    (net (code "53") (name "Net-(D21-A)") (class "Default")
      (node (ref "D21") (pin "1") (pinfunction "A_1") (pintype "passive"))
      (node (ref "D22") (pin "1") (pinfunction "A_1") (pintype "passive"))
      (node (ref "D23") (pin "1") (pinfunction "A_1") (pintype "passive"))
      (node (ref "D24") (pin "1") (pinfunction "A_1") (pintype "passive"))
      (node (ref "R94") (pin "2") (pinfunction "2_2") (pintype "passive"))
    )
    (net (code "54") (name "Net-(D25-A)") (class "Default")
      (node (ref "D25") (pin "1") (pinfunction "A_1") (pintype "passive"))
      (node (ref "D26") (pin "1") (pinfunction "A_1") (pintype "passive"))
      (node (ref "D27") (pin "1") (pinfunction "A_1") (pintype "passive"))
      (node (ref "D28") (pin "1") (pinfunction "A_1") (pintype "passive"))
      (node (ref "R95") (pin "2") (pinfunction "2_2") (pintype "passive"))
    )
    (net (code "55") (name "Net-(D29-A)") (class "Default")
      (node (ref "D29") (pin "1") (pinfunction "A_1") (pintype "passive"))
      (node (ref "D30") (pin "1") (pinfunction "A_1") (pintype "passive"))
      (node (ref "D31") (pin "1") (pinfunction "A_1") (pintype "passive"))
      (node (ref "D32") (pin "1") (pinfunction "A_1") (pintype "passive"))
      (node (ref "R96") (pin "2") (pinfunction "2_2") (pintype "passive"))
    )
    (net (code "56") (name "Net-(P15-Pad1)") (class "Default")
      (node (ref "P15") (pin "1") (pinfunction "1_1") (pintype "passive"))
      (node (ref "R13") (pin "1") (pinfunction "1_1") (pintype "passive"))
    )
    (net (code "57") (name "Net-(P15-Pad2)") (class "Default")
      (node (ref "P15") (pin "2") (pinfunction "2_2") (pintype "passive"))
      (node (ref "R23") (pin "1") (pinfunction "1_1") (pintype "passive"))
    )
    (net (code "58") (name "Net-(P15-Pad3)") (class "Default")
      (node (ref "P15") (pin "3") (pinfunction "3_3") (pintype "passive"))
      (node (ref "R33") (pin "1") (pinfunction "1_1") (pintype "passive"))
    )
    (net (code "59") (name "Net-(P15-Pad4)") (class "Default")
      (node (ref "P15") (pin "4") (pinfunction "4_4") (pintype "passive"))
      (node (ref "R43") (pin "1") (pinfunction "1_1") (pintype "passive"))
    )
    (net (code "60") (name "Net-(P15-Pad5)") (class "Default")
      (node (ref "P15") (pin "5") (pinfunction "5_5") (pintype "passive"))
      (node (ref "R53") (pin "1") (pinfunction "1_1") (pintype "passive"))
    )
    (net (code "61") (name "Net-(P15-Pad6)") (class "Default")
      (node (ref "P15") (pin "6") (pinfunction "6_6") (pintype "passive"))
      (node (ref "R63") (pin "1") (pinfunction "1_1") (pintype "passive"))
    )
    (net (code "62") (name "Net-(P15-Pad7)") (class "Default")
      (node (ref "P15") (pin "7") (pinfunction "7_7") (pintype "passive"))
      (node (ref "R73") (pin "1") (pinfunction "1_1") (pintype "passive"))
    )
    (net (code "63") (name "Net-(P15-Pad8)") (class "Default")
      (node (ref "P15") (pin "8") (pinfunction "8_8") (pintype "passive"))
      (node (ref "R83") (pin "1") (pinfunction "1_1") (pintype "passive"))
    )
    (net (code "64") (name "Net-(P15-Pad9)") (class "Default")
      (node (ref "P15") (pin "9") (pinfunction "9_9") (pintype "passive"))
      (node (ref "U11") (pin "2") (pinfunction "2_2") (pintype "passive"))
      (node (ref "U13") (pin "2") (pinfunction "2_2") (pintype "passive"))
      (node (ref "U15") (pin "2") (pinfunction "2_2") (pintype "passive"))
      (node (ref "U17") (pin "2") (pinfunction "2_2") (pintype "passive"))
      (node (ref "U19") (pin "2") (pinfunction "2_2") (pintype "passive"))
      (node (ref "U21") (pin "2") (pinfunction "2_2") (pintype "passive"))
      (node (ref "U23") (pin "2") (pinfunction "2_2") (pintype "passive"))
      (node (ref "U9") (pin "2") (pinfunction "2_2") (pintype "passive"))
    )
    (net (code "65") (name "Net-(P16-Pad1)") (class "Default")
      (node (ref "P16") (pin "1") (pinfunction "1_1") (pintype "passive"))
      (node (ref "R17") (pin "1") (pinfunction "1_1") (pintype "passive"))
    )
    (net (code "66") (name "Net-(P16-Pad2)") (class "Default")
      (node (ref "P16") (pin "2") (pinfunction "2_2") (pintype "passive"))
      (node (ref "R27") (pin "1") (pinfunction "1_1") (pintype "passive"))
    )
    (net (code "67") (name "Net-(P16-Pad3)") (class "Default")
      (node (ref "P16") (pin "3") (pinfunction "3_3") (pintype "passive"))
      (node (ref "R37") (pin "1") (pinfunction "1_1") (pintype "passive"))
    )
    (net (code "68") (name "Net-(P16-Pad4)") (class "Default")
      (node (ref "P16") (pin "4") (pinfunction "4_4") (pintype "passive"))
      (node (ref "R47") (pin "1") (pinfunction "1_1") (pintype "passive"))
    )
    (net (code "69") (name "Net-(P16-Pad5)") (class "Default")
      (node (ref "P16") (pin "5") (pinfunction "5_5") (pintype "passive"))
      (node (ref "R57") (pin "1") (pinfunction "1_1") (pintype "passive"))
    )
    (net (code "70") (name "Net-(P16-Pad6)") (class "Default")
      (node (ref "P16") (pin "6") (pinfunction "6_6") (pintype "passive"))
      (node (ref "R67") (pin "1") (pinfunction "1_1") (pintype "passive"))
    )
    (net (code "71") (name "Net-(P16-Pad7)") (class "Default")
      (node (ref "P16") (pin "7") (pinfunction "7_7") (pintype "passive"))
      (node (ref "R77") (pin "1") (pinfunction "1_1") (pintype "passive"))
    )
    (net (code "72") (name "Net-(P16-Pad8)") (class "Default")
      (node (ref "P16") (pin "8") (pinfunction "8_8") (pintype "passive"))
      (node (ref "R87") (pin "1") (pinfunction "1_1") (pintype "passive"))
    )
    (net (code "73") (name "Net-(P16-Pad9)") (class "Default")
      (node (ref "P16") (pin "9") (pinfunction "9_9") (pintype "passive"))
      (node (ref "U10") (pin "2") (pinfunction "2_2") (pintype "passive"))
      (node (ref "U12") (pin "2") (pinfunction "2_2") (pintype "passive"))
      (node (ref "U14") (pin "2") (pinfunction "2_2") (pintype "passive"))
      (node (ref "U16") (pin "2") (pinfunction "2_2") (pintype "passive"))
      (node (ref "U18") (pin "2") (pinfunction "2_2") (pintype "passive"))
      (node (ref "U20") (pin "2") (pinfunction "2_2") (pintype "passive"))
      (node (ref "U22") (pin "2") (pinfunction "2_2") (pintype "passive"))
      (node (ref "U24") (pin "2") (pinfunction "2_2") (pintype "passive"))
    )
    (net (code "74") (name "Net-(R13-Pad2)") (class "Default")
      (node (ref "R13") (pin "2") (pinfunction "2_2") (pintype "passive"))
      (node (ref "U9") (pin "1") (pinfunction "1_1") (pintype "passive"))
    )
    (net (code "75") (name "Net-(R14-Pad1)") (class "Default")
      (node (ref "R14") (pin "1") (pinfunction "1_1") (pintype "passive"))
      (node (ref "U9") (pin "6") (pinfunction "6_6") (pintype "passive"))
    )
    (net (code "76") (name "Net-(R14-Pad2)") (class "Default")
      (node (ref "R14") (pin "2") (pinfunction "2_2") (pintype "passive"))
      (node (ref "R15") (pin "1") (pinfunction "1_1") (pintype "passive"))
    )
    (net (code "77") (name "Net-(R15-Pad2)") (class "Default")
      (node (ref "R15") (pin "2") (pinfunction "2_2") (pintype "passive"))
      (node (ref "R16") (pin "1") (pinfunction "1_1") (pintype "passive"))
    )
    (net (code "78") (name "Net-(R17-Pad2)") (class "Default")
      (node (ref "R17") (pin "2") (pinfunction "2_2") (pintype "passive"))
      (node (ref "U10") (pin "1") (pinfunction "1_1") (pintype "passive"))
    )
    (net (code "79") (name "Net-(R18-Pad1)") (class "Default")
      (node (ref "R18") (pin "1") (pinfunction "1_1") (pintype "passive"))
      (node (ref "U10") (pin "6") (pinfunction "6_6") (pintype "passive"))
    )
    (net (code "80") (name "Net-(R18-Pad2)") (class "Default")
      (node (ref "R18") (pin "2") (pinfunction "2_2") (pintype "passive"))
      (node (ref "R19") (pin "1") (pinfunction "1_1") (pintype "passive"))
    )
    (net (code "81") (name "Net-(R19-Pad2)") (class "Default")
      (node (ref "R19") (pin "2") (pinfunction "2_2") (pintype "passive"))
      (node (ref "R20") (pin "1") (pinfunction "1_1") (pintype "passive"))
    )
    (net (code "82") (name "Net-(R23-Pad2)") (class "Default")
      (node (ref "R23") (pin "2") (pinfunction "2_2") (pintype "passive"))
      (node (ref "U11") (pin "1") (pinfunction "1_1") (pintype "passive"))
    )
    (net (code "83") (name "Net-(R24-Pad1)") (class "Default")
      (node (ref "R24") (pin "1") (pinfunction "1_1") (pintype "passive"))
      (node (ref "U11") (pin "6") (pinfunction "6_6") (pintype "passive"))
    )
    (net (code "84") (name "Net-(R24-Pad2)") (class "Default")
      (node (ref "R24") (pin "2") (pinfunction "2_2") (pintype "passive"))
      (node (ref "R25") (pin "1") (pinfunction "1_1") (pintype "passive"))
    )
    (net (code "85") (name "Net-(R25-Pad2)") (class "Default")
      (node (ref "R25") (pin "2") (pinfunction "2_2") (pintype "passive"))
      (node (ref "R26") (pin "1") (pinfunction "1_1") (pintype "passive"))
    )
    (net (code "86") (name "Net-(R27-Pad2)") (class "Default")
      (node (ref "R27") (pin "2") (pinfunction "2_2") (pintype "passive"))
      (node (ref "U12") (pin "1") (pinfunction "1_1") (pintype "passive"))
    )
    (net (code "87") (name "Net-(R28-Pad1)") (class "Default")
      (node (ref "R28") (pin "1") (pinfunction "1_1") (pintype "passive"))
      (node (ref "U12") (pin "6") (pinfunction "6_6") (pintype "passive"))
    )
    (net (code "88") (name "Net-(R28-Pad2)") (class "Default")
      (node (ref "R28") (pin "2") (pinfunction "2_2") (pintype "passive"))
      (node (ref "R29") (pin "1") (pinfunction "1_1") (pintype "passive"))
    )
    (net (code "89") (name "Net-(R29-Pad2)") (class "Default")
      (node (ref "R29") (pin "2") (pinfunction "2_2") (pintype "passive"))
      (node (ref "R30") (pin "1") (pinfunction "1_1") (pintype "passive"))
    )
    (net (code "90") (name "Net-(R33-Pad2)") (class "Default")
      (node (ref "R33") (pin "2") (pinfunction "2_2") (pintype "passive"))
      (node (ref "U13") (pin "1") (pinfunction "1_1") (pintype "passive"))
    )
    (net (code "91") (name "Net-(R34-Pad1)") (class "Default")
      (node (ref "R34") (pin "1") (pinfunction "1_1") (pintype "passive"))
      (node (ref "U13") (pin "6") (pinfunction "6_6") (pintype "passive"))
    )
    (net (code "92") (name "Net-(R34-Pad2)") (class "Default")
      (node (ref "R34") (pin "2") (pinfunction "2_2") (pintype "passive"))
      (node (ref "R35") (pin "1") (pinfunction "1_1") (pintype "passive"))
    )
    (net (code "93") (name "Net-(R35-Pad2)") (class "Default")
      (node (ref "R35") (pin "2") (pinfunction "2_2") (pintype "passive"))
      (node (ref "R36") (pin "1") (pinfunction "1_1") (pintype "passive"))
    )
    (net (code "94") (name "Net-(R37-Pad2)") (class "Default")
      (node (ref "R37") (pin "2") (pinfunction "2_2") (pintype "passive"))
      (node (ref "U14") (pin "1") (pinfunction "1_1") (pintype "passive"))
    )
    (net (code "95") (name "Net-(R38-Pad1)") (class "Default")
      (node (ref "R38") (pin "1") (pinfunction "1_1") (pintype "passive"))
      (node (ref "U14") (pin "6") (pinfunction "6_6") (pintype "passive"))
    )
    (net (code "96") (name "Net-(R38-Pad2)") (class "Default")
      (node (ref "R38") (pin "2") (pinfunction "2_2") (pintype "passive"))
      (node (ref "R39") (pin "1") (pinfunction "1_1") (pintype "passive"))
    )
    (net (code "97") (name "Net-(R39-Pad2)") (class "Default")
      (node (ref "R39") (pin "2") (pinfunction "2_2") (pintype "passive"))
      (node (ref "R40") (pin "1") (pinfunction "1_1") (pintype "passive"))
    )
    (net (code "98") (name "Net-(R43-Pad2)") (class "Default")
      (node (ref "R43") (pin "2") (pinfunction "2_2") (pintype "passive"))
      (node (ref "U15") (pin "1") (pinfunction "1_1") (pintype "passive"))
    )
    (net (code "99") (name "Net-(R44-Pad1)") (class "Default")
      (node (ref "R44") (pin "1") (pinfunction "1_1") (pintype "passive"))
      (node (ref "U15") (pin "6") (pinfunction "6_6") (pintype "passive"))
    )
    (net (code "100") (name "Net-(R44-Pad2)") (class "Default")
      (node (ref "R44") (pin "2") (pinfunction "2_2") (pintype "passive"))
      (node (ref "R45") (pin "1") (pinfunction "1_1") (pintype "passive"))
    )
    (net (code "101") (name "Net-(R45-Pad2)") (class "Default")
      (node (ref "R45") (pin "2") (pinfunction "2_2") (pintype "passive"))
      (node (ref "R46") (pin "1") (pinfunction "1_1") (pintype "passive"))
    )
    (net (code "102") (name "Net-(R47-Pad2)") (class "Default")
      (node (ref "R47") (pin "2") (pinfunction "2_2") (pintype "passive"))
      (node (ref "U16") (pin "1") (pinfunction "1_1") (pintype "passive"))
    )
    (net (code "103") (name "Net-(R48-Pad1)") (class "Default")
      (node (ref "R48") (pin "1") (pinfunction "1_1") (pintype "passive"))
      (node (ref "U16") (pin "6") (pinfunction "6_6") (pintype "passive"))
    )
    (net (code "104") (name "Net-(R48-Pad2)") (class "Default")
      (node (ref "R48") (pin "2") (pinfunction "2_2") (pintype "passive"))
      (node (ref "R49") (pin "1") (pinfunction "1_1") (pintype "passive"))
    )
    (net (code "105") (name "Net-(R49-Pad2)") (class "Default")
      (node (ref "R49") (pin "2") (pinfunction "2_2") (pintype "passive"))
      (node (ref "R50") (pin "1") (pinfunction "1_1") (pintype "passive"))
    )
    (net (code "106") (name "Net-(R53-Pad2)") (class "Default")
      (node (ref "R53") (pin "2") (pinfunction "2_2") (pintype "passive"))
      (node (ref "U17") (pin "1") (pinfunction "1_1") (pintype "passive"))
    )
    (net (code "107") (name "Net-(R54-Pad1)") (class "Default")
      (node (ref "R54") (pin "1") (pinfunction "1_1") (pintype "passive"))
      (node (ref "U17") (pin "6") (pinfunction "6_6") (pintype "passive"))
    )
    (net (code "108") (name "Net-(R54-Pad2)") (class "Default")
      (node (ref "R54") (pin "2") (pinfunction "2_2") (pintype "passive"))
      (node (ref "R55") (pin "1") (pinfunction "1_1") (pintype "passive"))
    )
    (net (code "109") (name "Net-(R55-Pad2)") (class "Default")
      (node (ref "R55") (pin "2") (pinfunction "2_2") (pintype "passive"))
      (node (ref "R56") (pin "1") (pinfunction "1_1") (pintype "passive"))
    )
    (net (code "110") (name "Net-(R57-Pad2)") (class "Default")
      (node (ref "R57") (pin "2") (pinfunction "2_2") (pintype "passive"))
      (node (ref "U18") (pin "1") (pinfunction "1_1") (pintype "passive"))
    )
    (net (code "111") (name "Net-(R58-Pad1)") (class "Default")
      (node (ref "R58") (pin "1") (pinfunction "1_1") (pintype "passive"))
      (node (ref "U18") (pin "6") (pinfunction "6_6") (pintype "passive"))
    )
    (net (code "112") (name "Net-(R58-Pad2)") (class "Default")
      (node (ref "R58") (pin "2") (pinfunction "2_2") (pintype "passive"))
      (node (ref "R59") (pin "1") (pinfunction "1_1") (pintype "passive"))
    )
    (net (code "113") (name "Net-(R59-Pad2)") (class "Default")
      (node (ref "R59") (pin "2") (pinfunction "2_2") (pintype "passive"))
      (node (ref "R60") (pin "1") (pinfunction "1_1") (pintype "passive"))
    )
    (net (code "114") (name "Net-(R63-Pad2)") (class "Default")
      (node (ref "R63") (pin "2") (pinfunction "2_2") (pintype "passive"))
      (node (ref "U19") (pin "1") (pinfunction "1_1") (pintype "passive"))
    )
    (net (code "115") (name "Net-(R64-Pad1)") (class "Default")
      (node (ref "R64") (pin "1") (pinfunction "1_1") (pintype "passive"))
      (node (ref "U19") (pin "6") (pinfunction "6_6") (pintype "passive"))
    )
    (net (code "116") (name "Net-(R64-Pad2)") (class "Default")
      (node (ref "R64") (pin "2") (pinfunction "2_2") (pintype "passive"))
      (node (ref "R65") (pin "1") (pinfunction "1_1") (pintype "passive"))
    )
    (net (code "117") (name "Net-(R65-Pad2)") (class "Default")
      (node (ref "R65") (pin "2") (pinfunction "2_2") (pintype "passive"))
      (node (ref "R66") (pin "1") (pinfunction "1_1") (pintype "passive"))
    )
    (net (code "118") (name "Net-(R67-Pad2)") (class "Default")
      (node (ref "R67") (pin "2") (pinfunction "2_2") (pintype "passive"))
      (node (ref "U20") (pin "1") (pinfunction "1_1") (pintype "passive"))
    )
    (net (code "119") (name "Net-(R68-Pad1)") (class "Default")
      (node (ref "R68") (pin "1") (pinfunction "1_1") (pintype "passive"))
      (node (ref "U20") (pin "6") (pinfunction "6_6") (pintype "passive"))
    )
    (net (code "120") (name "Net-(R68-Pad2)") (class "Default")
      (node (ref "R68") (pin "2") (pinfunction "2_2") (pintype "passive"))
      (node (ref "R69") (pin "1") (pinfunction "1_1") (pintype "passive"))
    )
    (net (code "121") (name "Net-(R69-Pad2)") (class "Default")
      (node (ref "R69") (pin "2") (pinfunction "2_2") (pintype "passive"))
      (node (ref "R70") (pin "1") (pinfunction "1_1") (pintype "passive"))
    )
    (net (code "122") (name "Net-(R73-Pad2)") (class "Default")
      (node (ref "R73") (pin "2") (pinfunction "2_2") (pintype "passive"))
      (node (ref "U21") (pin "1") (pinfunction "1_1") (pintype "passive"))
    )
    (net (code "123") (name "Net-(R74-Pad1)") (class "Default")
      (node (ref "R74") (pin "1") (pinfunction "1_1") (pintype "passive"))
      (node (ref "U21") (pin "6") (pinfunction "6_6") (pintype "passive"))
    )
    (net (code "124") (name "Net-(R74-Pad2)") (class "Default")
      (node (ref "R74") (pin "2") (pinfunction "2_2") (pintype "passive"))
      (node (ref "R75") (pin "1") (pinfunction "1_1") (pintype "passive"))
    )
    (net (code "125") (name "Net-(R75-Pad2)") (class "Default")
      (node (ref "R75") (pin "2") (pinfunction "2_2") (pintype "passive"))
      (node (ref "R76") (pin "1") (pinfunction "1_1") (pintype "passive"))
    )
    (net (code "126") (name "Net-(R77-Pad2)") (class "Default")
      (node (ref "R77") (pin "2") (pinfunction "2_2") (pintype "passive"))
      (node (ref "U22") (pin "1") (pinfunction "1_1") (pintype "passive"))
    )
    (net (code "127") (name "Net-(R78-Pad1)") (class "Default")
      (node (ref "R78") (pin "1") (pinfunction "1_1") (pintype "passive"))
      (node (ref "U22") (pin "6") (pinfunction "6_6") (pintype "passive"))
    )
    (net (code "128") (name "Net-(R78-Pad2)") (class "Default")
      (node (ref "R78") (pin "2") (pinfunction "2_2") (pintype "passive"))
      (node (ref "R79") (pin "1") (pinfunction "1_1") (pintype "passive"))
    )
    (net (code "129") (name "Net-(R79-Pad2)") (class "Default")
      (node (ref "R79") (pin "2") (pinfunction "2_2") (pintype "passive"))
      (node (ref "R80") (pin "1") (pinfunction "1_1") (pintype "passive"))
    )
    (net (code "130") (name "Net-(R83-Pad2)") (class "Default")
      (node (ref "R83") (pin "2") (pinfunction "2_2") (pintype "passive"))
      (node (ref "U23") (pin "1") (pinfunction "1_1") (pintype "passive"))
    )
    (net (code "131") (name "Net-(R84-Pad1)") (class "Default")
      (node (ref "R84") (pin "1") (pinfunction "1_1") (pintype "passive"))
      (node (ref "U23") (pin "6") (pinfunction "6_6") (pintype "passive"))
    )
    (net (code "132") (name "Net-(R84-Pad2)") (class "Default")
      (node (ref "R84") (pin "2") (pinfunction "2_2") (pintype "passive"))
      (node (ref "R85") (pin "1") (pinfunction "1_1") (pintype "passive"))
    )
    (net (code "133") (name "Net-(R85-Pad2)") (class "Default")
      (node (ref "R85") (pin "2") (pinfunction "2_2") (pintype "passive"))
      (node (ref "R86") (pin "1") (pinfunction "1_1") (pintype "passive"))
    )
    (net (code "134") (name "Net-(R87-Pad2)") (class "Default")
      (node (ref "R87") (pin "2") (pinfunction "2_2") (pintype "passive"))
      (node (ref "U24") (pin "1") (pinfunction "1_1") (pintype "passive"))
    )
    (net (code "135") (name "Net-(R88-Pad1)") (class "Default")
      (node (ref "R88") (pin "1") (pinfunction "1_1") (pintype "passive"))
      (node (ref "U24") (pin "6") (pinfunction "6_6") (pintype "passive"))
    )
    (net (code "136") (name "Net-(R88-Pad2)") (class "Default")
      (node (ref "R88") (pin "2") (pinfunction "2_2") (pintype "passive"))
      (node (ref "R89") (pin "1") (pinfunction "1_1") (pintype "passive"))
    )
    (net (code "137") (name "Net-(R89-Pad2)") (class "Default")
      (node (ref "R89") (pin "2") (pinfunction "2_2") (pintype "passive"))
      (node (ref "R90") (pin "1") (pinfunction "1_1") (pintype "passive"))
    )
    (net (code "138") (name "unconnected-(U9-Pad3)") (class "Default")
      (node (ref "U9") (pin "3") (pinfunction "3_3") (pintype "passive"))
    )
    (net (code "139") (name "unconnected-(U9-Pad5)") (class "Default")
      (node (ref "U9") (pin "5") (pinfunction "5_5") (pintype "passive"))
    )
    (net (code "140") (name "unconnected-(U10-Pad3)") (class "Default")
      (node (ref "U10") (pin "3") (pinfunction "3_3") (pintype "passive"))
    )
    (net (code "141") (name "unconnected-(U10-Pad5)") (class "Default")
      (node (ref "U10") (pin "5") (pinfunction "5_5") (pintype "passive"))
    )
    (net (code "142") (name "unconnected-(U11-Pad3)") (class "Default")
      (node (ref "U11") (pin "3") (pinfunction "3_3") (pintype "passive"))
    )
    (net (code "143") (name "unconnected-(U11-Pad5)") (class "Default")
      (node (ref "U11") (pin "5") (pinfunction "5_5") (pintype "passive"))
    )
    (net (code "144") (name "unconnected-(U12-Pad3)") (class "Default")
      (node (ref "U12") (pin "3") (pinfunction "3_3") (pintype "passive"))
    )
    (net (code "145") (name "unconnected-(U12-Pad5)") (class "Default")
      (node (ref "U12") (pin "5") (pinfunction "5_5") (pintype "passive"))
    )
    (net (code "146") (name "unconnected-(U13-Pad3)") (class "Default")
      (node (ref "U13") (pin "3") (pinfunction "3_3") (pintype "passive"))
    )
    (net (code "147") (name "unconnected-(U13-Pad5)") (class "Default")
      (node (ref "U13") (pin "5") (pinfunction "5_5") (pintype "passive"))
    )
    (net (code "148") (name "unconnected-(U14-Pad3)") (class "Default")
      (node (ref "U14") (pin "3") (pinfunction "3_3") (pintype "passive"))
    )
    (net (code "149") (name "unconnected-(U14-Pad5)") (class "Default")
      (node (ref "U14") (pin "5") (pinfunction "5_5") (pintype "passive"))
    )
    (net (code "150") (name "unconnected-(U15-Pad3)") (class "Default")
      (node (ref "U15") (pin "3") (pinfunction "3_3") (pintype "passive"))
    )
    (net (code "151") (name "unconnected-(U15-Pad5)") (class "Default")
      (node (ref "U15") (pin "5") (pinfunction "5_5") (pintype "passive"))
    )
    (net (code "152") (name "unconnected-(U16-Pad3)") (class "Default")
      (node (ref "U16") (pin "3") (pinfunction "3_3") (pintype "passive"))
    )
    (net (code "153") (name "unconnected-(U16-Pad5)") (class "Default")
      (node (ref "U16") (pin "5") (pinfunction "5_5") (pintype "passive"))
    )
    (net (code "154") (name "unconnected-(U17-Pad3)") (class "Default")
      (node (ref "U17") (pin "3") (pinfunction "3_3") (pintype "passive"))
    )
    (net (code "155") (name "unconnected-(U17-Pad5)") (class "Default")
      (node (ref "U17") (pin "5") (pinfunction "5_5") (pintype "passive"))
    )
    (net (code "156") (name "unconnected-(U18-Pad3)") (class "Default")
      (node (ref "U18") (pin "3") (pinfunction "3_3") (pintype "passive"))
    )
    (net (code "157") (name "unconnected-(U18-Pad5)") (class "Default")
      (node (ref "U18") (pin "5") (pinfunction "5_5") (pintype "passive"))
    )
    (net (code "158") (name "unconnected-(U19-Pad3)") (class "Default")
      (node (ref "U19") (pin "3") (pinfunction "3_3") (pintype "passive"))
    )
    (net (code "159") (name "unconnected-(U19-Pad5)") (class "Default")
      (node (ref "U19") (pin "5") (pinfunction "5_5") (pintype "passive"))
    )
    (net (code "160") (name "unconnected-(U20-Pad3)") (class "Default")
      (node (ref "U20") (pin "3") (pinfunction "3_3") (pintype "passive"))
    )
    (net (code "161") (name "unconnected-(U20-Pad5)") (class "Default")
      (node (ref "U20") (pin "5") (pinfunction "5_5") (pintype "passive"))
    )
    (net (code "162") (name "unconnected-(U21-Pad3)") (class "Default")
      (node (ref "U21") (pin "3") (pinfunction "3_3") (pintype "passive"))
    )
    (net (code "163") (name "unconnected-(U21-Pad5)") (class "Default")
      (node (ref "U21") (pin "5") (pinfunction "5_5") (pintype "passive"))
    )
    (net (code "164") (name "unconnected-(U22-Pad3)") (class "Default")
      (node (ref "U22") (pin "3") (pinfunction "3_3") (pintype "passive"))
    )
    (net (code "165") (name "unconnected-(U22-Pad5)") (class "Default")
      (node (ref "U22") (pin "5") (pinfunction "5_5") (pintype "passive"))
    )
    (net (code "166") (name "unconnected-(U23-Pad3)") (class "Default")
      (node (ref "U23") (pin "3") (pinfunction "3_3") (pintype "passive"))
    )
    (net (code "167") (name "unconnected-(U23-Pad5)") (class "Default")
      (node (ref "U23") (pin "5") (pinfunction "5_5") (pintype "passive"))
    )
    (net (code "168") (name "unconnected-(U24-Pad3)") (class "Default")
      (node (ref "U24") (pin "3") (pinfunction "3_3") (pintype "passive"))
    )
    (net (code "169") (name "unconnected-(U24-Pad5)") (class "Default")
      (node (ref "U24") (pin "5") (pinfunction "5_5") (pintype "passive"))
    )
  )
)
